# i2c_bargraph.net
KiCad netlist of a schematic drawn in EAGLE
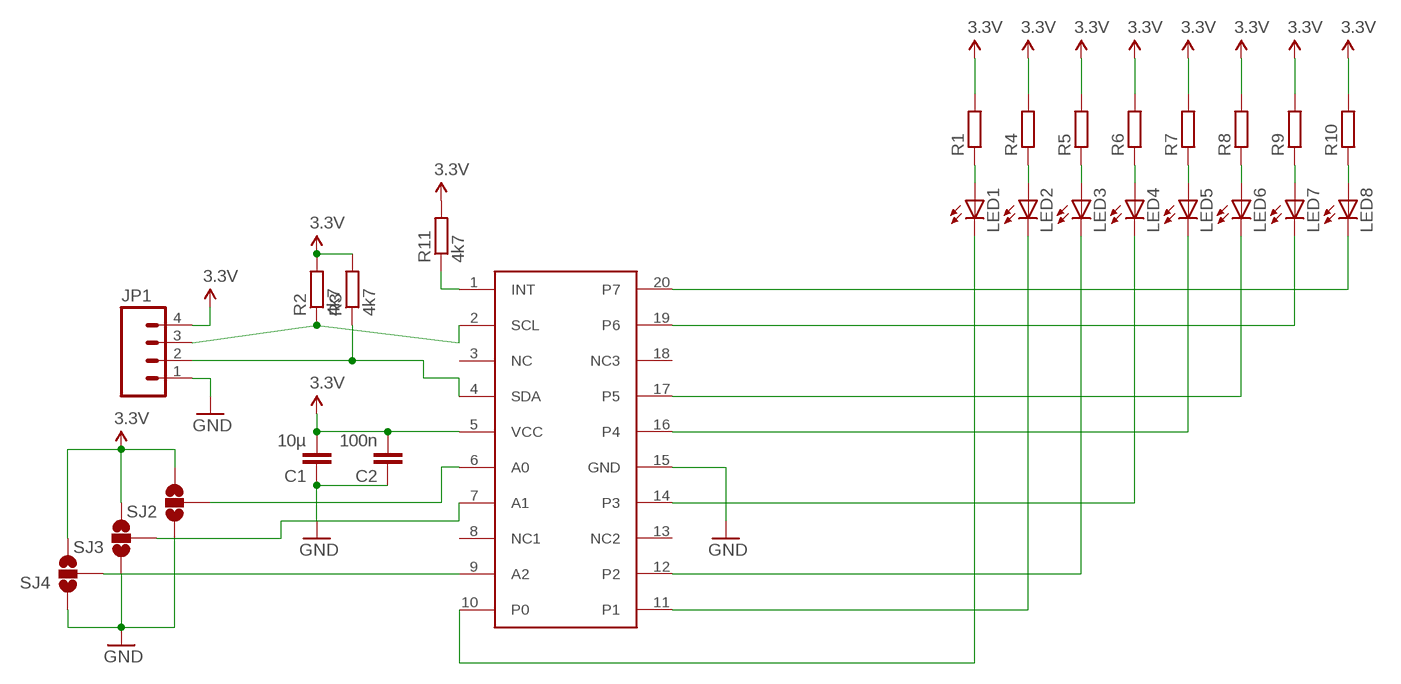
[diagram p0: schematic, sheet 1]

(export (version "E")
  (design (tool "Eeschema 10.0.6"))
  (components
    (comp (ref "C1")
      (value "10µ")
      (footprint "eagle-import:C0603")
      (libsource (lib "eagle-import") (part "C-EUC0603"))
    )
    (comp (ref "C2")
      (value "100n")
      (footprint "eagle-import:C0603")
      (libsource (lib "eagle-import") (part "C-EUC0603"))
    )
    (comp (ref "JP1")
      (value "M04PTH")
      (footprint "eagle-import:1X04")
      (libsource (lib "eagle-import") (part "M04PTH"))
    )
    (comp (ref "LED1")
      (value "LEDCHIP-LED0805")
      (footprint "eagle-import:CHIP-LED0805")
      (libsource (lib "eagle-import") (part "LEDCHIP-LED0805"))
    )
    (comp (ref "LED2")
      (value "LEDCHIP-LED0805")
      (footprint "eagle-import:CHIP-LED0805")
      (libsource (lib "eagle-import") (part "LEDCHIP-LED0805"))
    )
    (comp (ref "LED3")
      (value "LEDCHIP-LED0805")
      (footprint "eagle-import:CHIP-LED0805")
      (libsource (lib "eagle-import") (part "LEDCHIP-LED0805"))
    )
    (comp (ref "LED4")
      (value "LEDCHIP-LED0805")
      (footprint "eagle-import:CHIP-LED0805")
      (libsource (lib "eagle-import") (part "LEDCHIP-LED0805"))
    )
    (comp (ref "LED5")
      (value "LEDCHIP-LED0805")
      (footprint "eagle-import:CHIP-LED0805")
      (libsource (lib "eagle-import") (part "LEDCHIP-LED0805"))
    )
    (comp (ref "LED6")
      (value "LEDCHIP-LED0805")
      (footprint "eagle-import:CHIP-LED0805")
      (libsource (lib "eagle-import") (part "LEDCHIP-LED0805"))
    )
    (comp (ref "LED7")
      (value "LEDCHIP-LED0805")
      (footprint "eagle-import:CHIP-LED0805")
      (libsource (lib "eagle-import") (part "LEDCHIP-LED0805"))
    )
    (comp (ref "LED8")
      (value "LEDCHIP-LED0805")
      (footprint "eagle-import:CHIP-LED0805")
      (libsource (lib "eagle-import") (part "LEDCHIP-LED0805"))
    )
    (comp (ref "R1")
      (value "R-EU_R0603")
      (footprint "eagle-import:R0603")
      (libsource (lib "eagle-import") (part "R-EU_R0603"))
    )
    (comp (ref "R2")
      (value "4k7")
      (footprint "eagle-import:R0603")
      (libsource (lib "eagle-import") (part "R-EU_R0603"))
    )
    (comp (ref "R3")
      (value "4k7")
      (footprint "eagle-import:R0603")
      (libsource (lib "eagle-import") (part "R-EU_R0603"))
    )
    (comp (ref "R4")
      (value "R-EU_R0603")
      (footprint "eagle-import:R0603")
      (libsource (lib "eagle-import") (part "R-EU_R0603"))
    )
    (comp (ref "R5")
      (value "R-EU_R0603")
      (footprint "eagle-import:R0603")
      (libsource (lib "eagle-import") (part "R-EU_R0603"))
    )
    (comp (ref "R6")
      (value "R-EU_R0603")
      (footprint "eagle-import:R0603")
      (libsource (lib "eagle-import") (part "R-EU_R0603"))
    )
    (comp (ref "R7")
      (value "R-EU_R0603")
      (footprint "eagle-import:R0603")
      (libsource (lib "eagle-import") (part "R-EU_R0603"))
    )
    (comp (ref "R8")
      (value "R-EU_R0603")
      (footprint "eagle-import:R0603")
      (libsource (lib "eagle-import") (part "R-EU_R0603"))
    )
    (comp (ref "R9")
      (value "R-EU_R0603")
      (footprint "eagle-import:R0603")
      (libsource (lib "eagle-import") (part "R-EU_R0603"))
    )
    (comp (ref "R10")
      (value "R-EU_R0603")
      (footprint "eagle-import:R0603")
      (libsource (lib "eagle-import") (part "R-EU_R0603"))
    )
    (comp (ref "R11")
      (value "4k7")
      (footprint "eagle-import:R0603")
      (libsource (lib "eagle-import") (part "R-EU_R0603"))
    )
    (comp (ref "SJ2")
      (value "SOLDERJUMPER_2WAY-OLDS")
      (footprint "eagle-import:SJ_3")
      (libsource (lib "eagle-import") (part "SOLDERJUMPER_2WAY-OLDS"))
    )
    (comp (ref "SJ3")
      (value "SOLDERJUMPER_2WAY-OLDS")
      (footprint "eagle-import:SJ_3")
      (libsource (lib "eagle-import") (part "SOLDERJUMPER_2WAY-OLDS"))
    )
    (comp (ref "SJ4")
      (value "SOLDERJUMPER_2WAY-OLDS")
      (footprint "eagle-import:SJ_3")
      (libsource (lib "eagle-import") (part "SOLDERJUMPER_2WAY-OLDS"))
    )
    (comp (ref "U$1")
      (value "PCF8574TSSOP")
      (footprint "eagle-import:TSSOP20")
      (libsource (lib "eagle-import") (part "PCF8574TSSOP"))
    )
  )
  (nets
    (net (code "1") (name "3.3V") (class "Default")
      (node (ref "C1") (pin "2") (pinfunction "2_2") (pintype "passive"))
      (node (ref "C2") (pin "2") (pinfunction "2_2") (pintype "passive"))
      (node (ref "JP1") (pin "4") (pinfunction "4_4") (pintype "passive"))
      (node (ref "R1") (pin "2") (pinfunction "2_2") (pintype "passive"))
      (node (ref "R10") (pin "2") (pinfunction "2_2") (pintype "passive"))
      (node (ref "R11") (pin "2") (pinfunction "2_2") (pintype "passive"))
      (node (ref "R2") (pin "2") (pinfunction "2_2") (pintype "passive"))
      (node (ref "R3") (pin "2") (pinfunction "2_2") (pintype "passive"))
      (node (ref "R4") (pin "2") (pinfunction "2_2") (pintype "passive"))
      (node (ref "R5") (pin "2") (pinfunction "2_2") (pintype "passive"))
      (node (ref "R6") (pin "2") (pinfunction "2_2") (pintype "passive"))
      (node (ref "R7") (pin "2") (pinfunction "2_2") (pintype "passive"))
      (node (ref "R8") (pin "2") (pinfunction "2_2") (pintype "passive"))
      (node (ref "R9") (pin "2") (pinfunction "2_2") (pintype "passive"))
      (node (ref "SJ2") (pin "3") (pinfunction "3_3") (pintype "passive"))
      (node (ref "SJ3") (pin "3") (pinfunction "3_3") (pintype "passive"))
      (node (ref "SJ4") (pin "3") (pinfunction "3_3") (pintype "passive"))
      (node (ref "U$1") (pin "5") (pinfunction "VCC_5") (pintype "bidirectional"))
    )
    (net (code "2") (name "GND") (class "Default")
      (node (ref "C1") (pin "1") (pinfunction "1_1") (pintype "passive"))
      (node (ref "C2") (pin "1") (pinfunction "1_1") (pintype "passive"))
      (node (ref "JP1") (pin "1") (pinfunction "1_1") (pintype "passive"))
      (node (ref "SJ2") (pin "1") (pinfunction "1_1") (pintype "passive"))
      (node (ref "SJ3") (pin "1") (pinfunction "1_1") (pintype "passive"))
      (node (ref "SJ4") (pin "1") (pinfunction "1_1") (pintype "passive"))
      (node (ref "U$1") (pin "15") (pinfunction "GND_15") (pintype "bidirectional"))
    )
    (net (code "3") (name "Net-(LED1-PadA)") (class "Default")
      (node (ref "LED1") (pin "A") (pinfunction "A_A") (pintype "passive"))
      (node (ref "R1") (pin "1") (pinfunction "1_1") (pintype "passive"))
    )
    (net (code "4") (name "Net-(LED2-PadA)") (class "Default")
      (node (ref "LED2") (pin "A") (pinfunction "A_A") (pintype "passive"))
      (node (ref "R4") (pin "1") (pinfunction "1_1") (pintype "passive"))
    )
    (net (code "5") (name "Net-(LED3-PadA)") (class "Default")
      (node (ref "LED3") (pin "A") (pinfunction "A_A") (pintype "passive"))
      (node (ref "R5") (pin "1") (pinfunction "1_1") (pintype "passive"))
    )
    (net (code "6") (name "Net-(LED4-PadA)") (class "Default")
      (node (ref "LED4") (pin "A") (pinfunction "A_A") (pintype "passive"))
      (node (ref "R6") (pin "1") (pinfunction "1_1") (pintype "passive"))
    )
    (net (code "7") (name "Net-(LED5-PadA)") (class "Default")
      (node (ref "LED5") (pin "A") (pinfunction "A_A") (pintype "passive"))
      (node (ref "R7") (pin "1") (pinfunction "1_1") (pintype "passive"))
    )
    (net (code "8") (name "Net-(LED6-PadA)") (class "Default")
      (node (ref "LED6") (pin "A") (pinfunction "A_A") (pintype "passive"))
      (node (ref "R8") (pin "1") (pinfunction "1_1") (pintype "passive"))
    )
    (net (code "9") (name "Net-(LED7-PadA)") (class "Default")
      (node (ref "LED7") (pin "A") (pinfunction "A_A") (pintype "passive"))
      (node (ref "R9") (pin "1") (pinfunction "1_1") (pintype "passive"))
    )
    (net (code "10") (name "Net-(LED8-PadA)") (class "Default")
      (node (ref "LED8") (pin "A") (pinfunction "A_A") (pintype "passive"))
      (node (ref "R10") (pin "1") (pinfunction "1_1") (pintype "passive"))
    )
    (net (code "11") (name "Net-(U$1-A0)") (class "Default")
      (node (ref "SJ2") (pin "2") (pinfunction "2_2") (pintype "passive"))
      (node (ref "U$1") (pin "6") (pinfunction "A0_6") (pintype "bidirectional"))
    )
    (net (code "12") (name "Net-(U$1-A1)") (class "Default")
      (node (ref "SJ3") (pin "2") (pinfunction "2_2") (pintype "passive"))
      (node (ref "U$1") (pin "7") (pinfunction "A1_7") (pintype "bidirectional"))
    )
    (net (code "13") (name "Net-(U$1-A2)") (class "Default")
      (node (ref "SJ4") (pin "2") (pinfunction "2_2") (pintype "passive"))
      (node (ref "U$1") (pin "9") (pinfunction "A2_9") (pintype "bidirectional"))
    )
    (net (code "14") (name "Net-(U$1-INT)") (class "Default")
      (node (ref "R11") (pin "1") (pinfunction "1_1") (pintype "passive"))
      (node (ref "U$1") (pin "1") (pinfunction "INT_1") (pintype "bidirectional"))
    )
    (net (code "15") (name "Net-(U$1-P0)") (class "Default")
      (node (ref "LED1") (pin "C") (pinfunction "C_C") (pintype "passive"))
      (node (ref "U$1") (pin "10") (pinfunction "P0_10") (pintype "bidirectional"))
    )
    (net (code "16") (name "Net-(U$1-P1)") (class "Default")
      (node (ref "LED2") (pin "C") (pinfunction "C_C") (pintype "passive"))
      (node (ref "U$1") (pin "11") (pinfunction "P1_11") (pintype "bidirectional"))
    )
    (net (code "17") (name "Net-(U$1-P2)") (class "Default")
      (node (ref "LED3") (pin "C") (pinfunction "C_C") (pintype "passive"))
      (node (ref "U$1") (pin "12") (pinfunction "P2_12") (pintype "bidirectional"))
    )
    (net (code "18") (name "Net-(U$1-P3)") (class "Default")
      (node (ref "LED4") (pin "C") (pinfunction "C_C") (pintype "passive"))
      (node (ref "U$1") (pin "14") (pinfunction "P3_14") (pintype "bidirectional"))
    )
    (net (code "19") (name "Net-(U$1-P4)") (class "Default")
      (node (ref "LED5") (pin "C") (pinfunction "C_C") (pintype "passive"))
      (node (ref "U$1") (pin "16") (pinfunction "P4_16") (pintype "bidirectional"))
    )
    (net (code "20") (name "Net-(U$1-P5)") (class "Default")
      (node (ref "LED6") (pin "C") (pinfunction "C_C") (pintype "passive"))
      (node (ref "U$1") (pin "17") (pinfunction "P5_17") (pintype "bidirectional"))
    )
    (net (code "21") (name "Net-(U$1-P6)") (class "Default")
      (node (ref "LED7") (pin "C") (pinfunction "C_C") (pintype "passive"))
      (node (ref "U$1") (pin "19") (pinfunction "P6_19") (pintype "bidirectional"))
    )
    (net (code "22") (name "Net-(U$1-P7)") (class "Default")
      (node (ref "LED8") (pin "C") (pinfunction "C_C") (pintype "passive"))
      (node (ref "U$1") (pin "20") (pinfunction "P7_20") (pintype "bidirectional"))
    )
    (net (code "23") (name "Net-(U$1-SCL)") (class "Default")
      (node (ref "JP1") (pin "3") (pinfunction "3_3") (pintype "passive"))
      (node (ref "R2") (pin "1") (pinfunction "1_1") (pintype "passive"))
      (node (ref "U$1") (pin "2") (pinfunction "SCL_2") (pintype "bidirectional"))
    )
    (net (code "24") (name "Net-(U$1-SDA)") (class "Default")
      (node (ref "JP1") (pin "2") (pinfunction "2_2") (pintype "passive"))
      (node (ref "R3") (pin "1") (pinfunction "1_1") (pintype "passive"))
      (node (ref "U$1") (pin "4") (pinfunction "SDA_4") (pintype "bidirectional"))
    )
    (net (code "25") (name "unconnected-(U$1-NC-Pad3)") (class "Default")
      (node (ref "U$1") (pin "3") (pinfunction "NC_3") (pintype "bidirectional"))
    )
    (net (code "26") (name "unconnected-(U$1-NC1-Pad8)") (class "Default")
      (node (ref "U$1") (pin "8") (pinfunction "NC1_8") (pintype "bidirectional"))
    )
    (net (code "27") (name "unconnected-(U$1-NC2-Pad13)") (class "Default")
      (node (ref "U$1") (pin "13") (pinfunction "NC2_13") (pintype "bidirectional"))
    )
    (net (code "28") (name "unconnected-(U$1-NC3-Pad18)") (class "Default")
      (node (ref "U$1") (pin "18") (pinfunction "NC3_18") (pintype "bidirectional"))
    )
  )
)
